# SparkFun_I2C_Expander-PCF8575.net
KiCad netlist of a schematic drawn in EAGLE
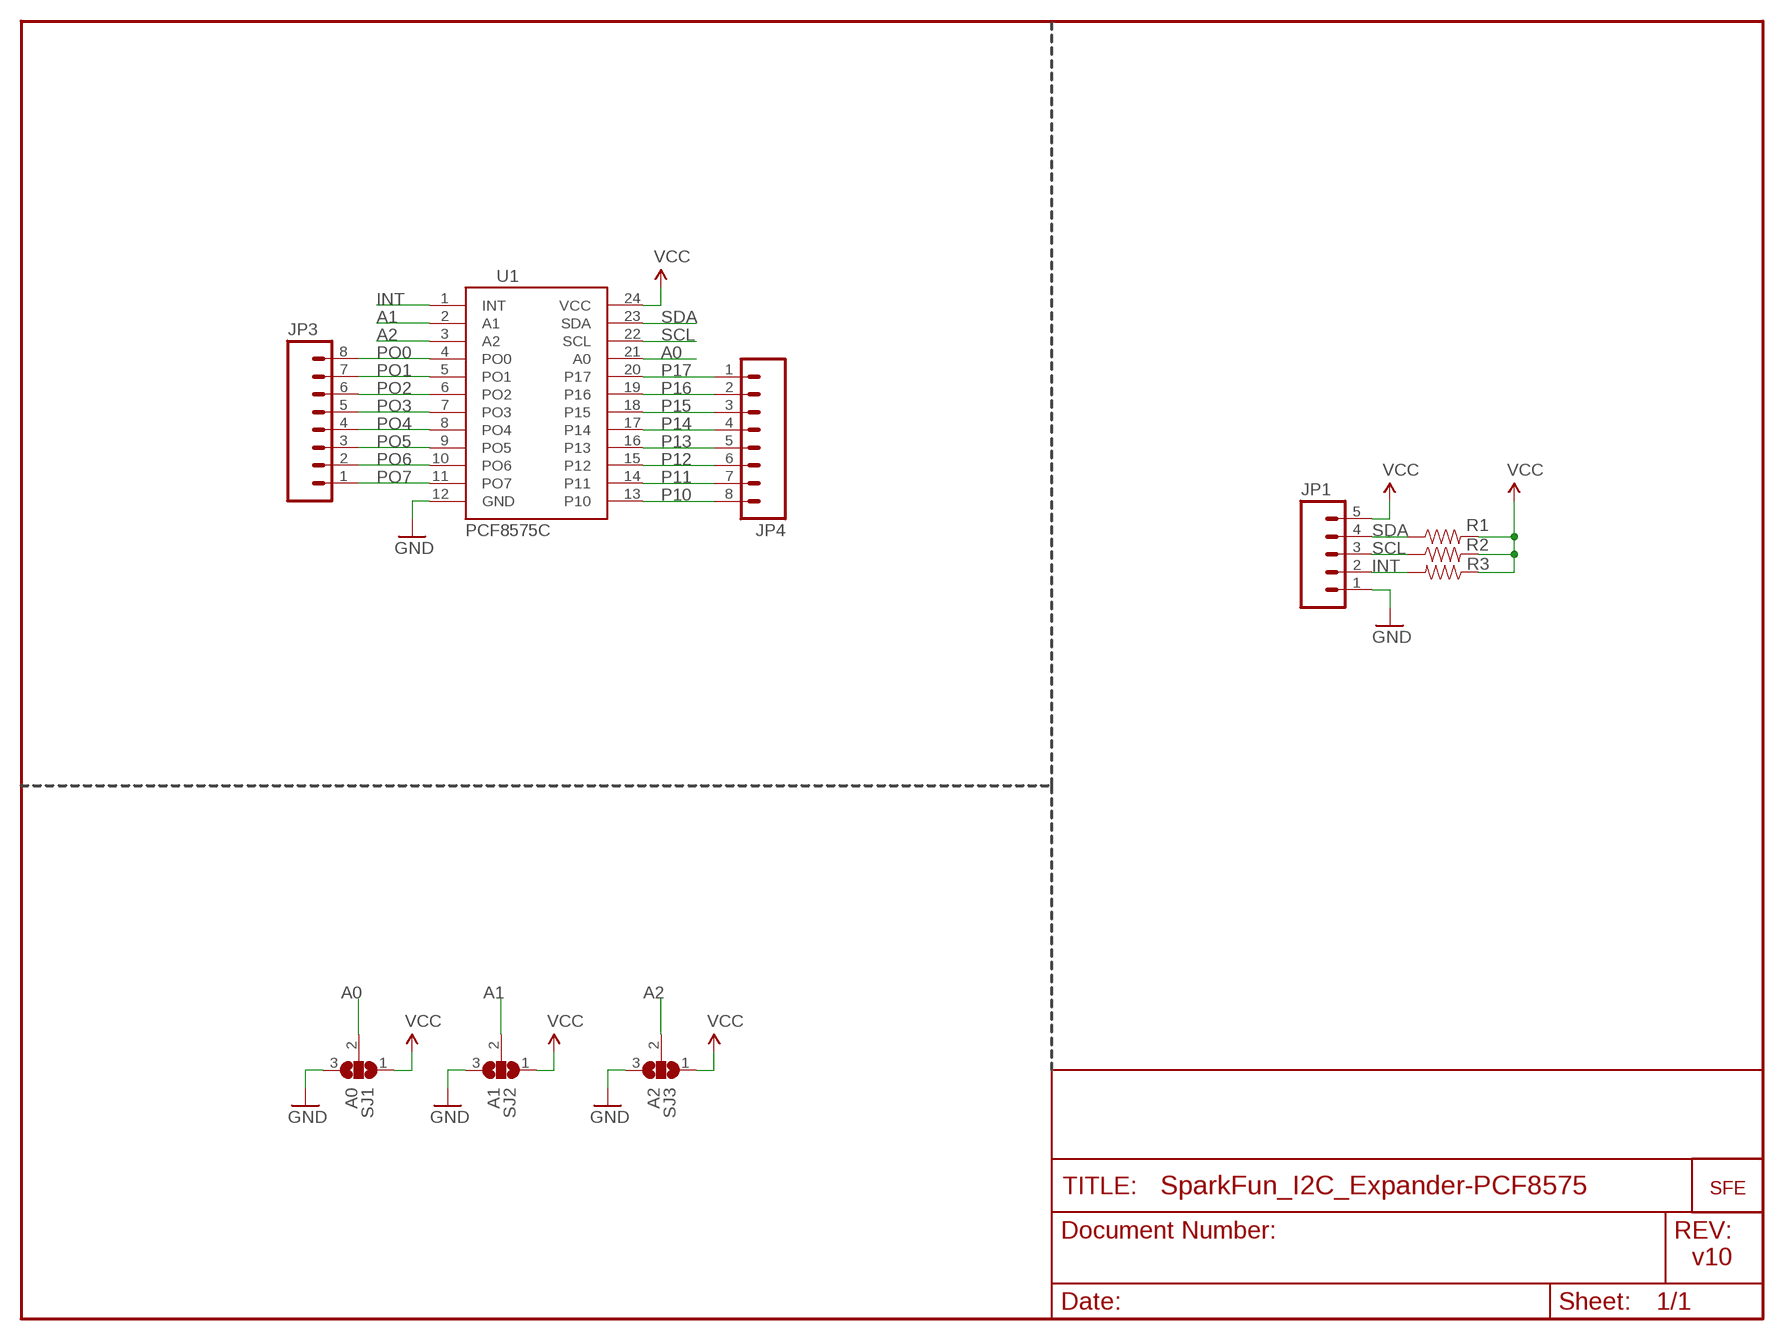
[diagram p0: schematic, sheet 1]

(export (version "E")
  (design (tool "Eeschema 10.0.6"))
  (components
    (comp (ref "JP1")
      (value "M05")
      (footprint "eagle-import:1X05")
      (libsource (lib "eagle-import") (part "M05"))
    )
    (comp (ref "JP3")
      (value "M08")
      (footprint "eagle-import:1X08")
      (libsource (lib "eagle-import") (part "M08"))
    )
    (comp (ref "JP4")
      (value "M08")
      (footprint "eagle-import:1X08")
      (libsource (lib "eagle-import") (part "M08"))
    )
    (comp (ref "R1")
      (value "RESISTOR0402")
      (footprint "eagle-import:C0402")
      (libsource (lib "eagle-import") (part "RESISTOR0402"))
    )
    (comp (ref "R2")
      (value "RESISTOR0402")
      (footprint "eagle-import:C0402")
      (libsource (lib "eagle-import") (part "RESISTOR0402"))
    )
    (comp (ref "R3")
      (value "RESISTOR0402")
      (footprint "eagle-import:C0402")
      (libsource (lib "eagle-import") (part "RESISTOR0402"))
    )
    (comp (ref "SJ1")
      (value "A0")
      (footprint "eagle-import:SJ_3")
      (libsource (lib "eagle-import") (part "SOLDERJUMPER_2WAYS"))
    )
    (comp (ref "SJ2")
      (value "A1")
      (footprint "eagle-import:SJ_3")
      (libsource (lib "eagle-import") (part "SOLDERJUMPER_2WAYS"))
    )
    (comp (ref "SJ3")
      (value "A2")
      (footprint "eagle-import:SJ_3")
      (libsource (lib "eagle-import") (part "SOLDERJUMPER_2WAYS"))
    )
    (comp (ref "U$2")
      (value "LOGO-SFENEW")
      (footprint "eagle-import:SFE-NEW-WEBLOGO")
      (libsource (lib "eagle-import") (part "LOGO-SFENEW"))
    )
    (comp (ref "U1")
      (value "PCF8575C")
      (footprint "eagle-import:SO-24DW")
      (libsource (lib "eagle-import") (part "PCF8575C"))
    )
  )
  (nets
    (net (code "1") (name "/A0") (class "Default")
      (node (ref "SJ1") (pin "2") (pinfunction "2_2") (pintype "passive"))
      (node (ref "U1") (pin "21") (pinfunction "A0_21") (pintype "bidirectional"))
    )
    (net (code "2") (name "/A1") (class "Default")
      (node (ref "SJ2") (pin "2") (pinfunction "2_2") (pintype "passive"))
      (node (ref "U1") (pin "2") (pinfunction "A1_2") (pintype "bidirectional"))
    )
    (net (code "3") (name "/A2") (class "Default")
      (node (ref "SJ3") (pin "2") (pinfunction "2_2") (pintype "passive"))
      (node (ref "U1") (pin "3") (pinfunction "A2_3") (pintype "bidirectional"))
    )
    (net (code "4") (name "/INT") (class "Default")
      (node (ref "JP1") (pin "2") (pinfunction "2_2") (pintype "passive"))
      (node (ref "R3") (pin "2") (pinfunction "2_2") (pintype "passive"))
      (node (ref "U1") (pin "1") (pinfunction "INT_1") (pintype "bidirectional"))
    )
    (net (code "5") (name "/P10") (class "Default")
      (node (ref "JP4") (pin "8") (pinfunction "8_8") (pintype "passive"))
      (node (ref "U1") (pin "13") (pinfunction "P10_13") (pintype "bidirectional"))
    )
    (net (code "6") (name "/P11") (class "Default")
      (node (ref "JP4") (pin "7") (pinfunction "7_7") (pintype "passive"))
      (node (ref "U1") (pin "14") (pinfunction "P11_14") (pintype "bidirectional"))
    )
    (net (code "7") (name "/P12") (class "Default")
      (node (ref "JP4") (pin "6") (pinfunction "6_6") (pintype "passive"))
      (node (ref "U1") (pin "15") (pinfunction "P12_15") (pintype "bidirectional"))
    )
    (net (code "8") (name "/P13") (class "Default")
      (node (ref "JP4") (pin "5") (pinfunction "5_5") (pintype "passive"))
      (node (ref "U1") (pin "16") (pinfunction "P13_16") (pintype "bidirectional"))
    )
    (net (code "9") (name "/P14") (class "Default")
      (node (ref "JP4") (pin "4") (pinfunction "4_4") (pintype "passive"))
      (node (ref "U1") (pin "17") (pinfunction "P14_17") (pintype "bidirectional"))
    )
    (net (code "10") (name "/P15") (class "Default")
      (node (ref "JP4") (pin "3") (pinfunction "3_3") (pintype "passive"))
      (node (ref "U1") (pin "18") (pinfunction "P15_18") (pintype "bidirectional"))
    )
    (net (code "11") (name "/P16") (class "Default")
      (node (ref "JP4") (pin "2") (pinfunction "2_2") (pintype "passive"))
      (node (ref "U1") (pin "19") (pinfunction "P16_19") (pintype "bidirectional"))
    )
    (net (code "12") (name "/P17") (class "Default")
      (node (ref "JP4") (pin "1") (pinfunction "1_1") (pintype "passive"))
      (node (ref "U1") (pin "20") (pinfunction "P17_20") (pintype "bidirectional"))
    )
    (net (code "13") (name "/PO0") (class "Default")
      (node (ref "JP3") (pin "8") (pinfunction "8_8") (pintype "passive"))
      (node (ref "U1") (pin "4") (pinfunction "PO0_4") (pintype "bidirectional"))
    )
    (net (code "14") (name "/PO1") (class "Default")
      (node (ref "JP3") (pin "7") (pinfunction "7_7") (pintype "passive"))
      (node (ref "U1") (pin "5") (pinfunction "PO1_5") (pintype "bidirectional"))
    )
    (net (code "15") (name "/PO2") (class "Default")
      (node (ref "JP3") (pin "6") (pinfunction "6_6") (pintype "passive"))
      (node (ref "U1") (pin "6") (pinfunction "PO2_6") (pintype "bidirectional"))
    )
    (net (code "16") (name "/PO3") (class "Default")
      (node (ref "JP3") (pin "5") (pinfunction "5_5") (pintype "passive"))
      (node (ref "U1") (pin "7") (pinfunction "PO3_7") (pintype "bidirectional"))
    )
    (net (code "17") (name "/PO4") (class "Default")
      (node (ref "JP3") (pin "4") (pinfunction "4_4") (pintype "passive"))
      (node (ref "U1") (pin "8") (pinfunction "PO4_8") (pintype "bidirectional"))
    )
    (net (code "18") (name "/PO5") (class "Default")
      (node (ref "JP3") (pin "3") (pinfunction "3_3") (pintype "passive"))
      (node (ref "U1") (pin "9") (pinfunction "PO5_9") (pintype "bidirectional"))
    )
    (net (code "19") (name "/PO6") (class "Default")
      (node (ref "JP3") (pin "2") (pinfunction "2_2") (pintype "passive"))
      (node (ref "U1") (pin "10") (pinfunction "PO6_10") (pintype "bidirectional"))
    )
    (net (code "20") (name "/PO7") (class "Default")
      (node (ref "JP3") (pin "1") (pinfunction "1_1") (pintype "passive"))
      (node (ref "U1") (pin "11") (pinfunction "PO7_11") (pintype "bidirectional"))
    )
    (net (code "21") (name "/SCL") (class "Default")
      (node (ref "JP1") (pin "3") (pinfunction "3_3") (pintype "passive"))
      (node (ref "R2") (pin "1") (pinfunction "1_1") (pintype "passive"))
      (node (ref "U1") (pin "22") (pinfunction "SCL_22") (pintype "bidirectional"))
    )
    (net (code "22") (name "/SDA") (class "Default")
      (node (ref "JP1") (pin "4") (pinfunction "4_4") (pintype "passive"))
      (node (ref "R1") (pin "1") (pinfunction "1_1") (pintype "passive"))
      (node (ref "U1") (pin "23") (pinfunction "SDA_23") (pintype "bidirectional"))
    )
    (net (code "23") (name "GND") (class "Default")
      (node (ref "JP1") (pin "1") (pinfunction "1_1") (pintype "passive"))
      (node (ref "SJ1") (pin "3") (pinfunction "3_3") (pintype "passive"))
      (node (ref "SJ2") (pin "3") (pinfunction "3_3") (pintype "passive"))
      (node (ref "SJ3") (pin "3") (pinfunction "3_3") (pintype "passive"))
      (node (ref "U1") (pin "12") (pinfunction "GND_12") (pintype "bidirectional"))
    )
    (net (code "24") (name "VCC") (class "Default")
      (node (ref "JP1") (pin "5") (pinfunction "5_5") (pintype "passive"))
      (node (ref "R1") (pin "2") (pinfunction "2_2") (pintype "passive"))
      (node (ref "R2") (pin "2") (pinfunction "2_2") (pintype "passive"))
      (node (ref "R3") (pin "1") (pinfunction "1_1") (pintype "passive"))
      (node (ref "SJ1") (pin "1") (pinfunction "1_1") (pintype "passive"))
      (node (ref "SJ2") (pin "1") (pinfunction "1_1") (pintype "passive"))
      (node (ref "SJ3") (pin "1") (pinfunction "1_1") (pintype "passive"))
      (node (ref "U1") (pin "24") (pinfunction "VCC_24") (pintype "bidirectional"))
    )
  )
)
